# S7CAS-PLEIADES-CARTE-MERE_P06_ADC.net
KiCad netlist of a schematic drawn in Altium Designer
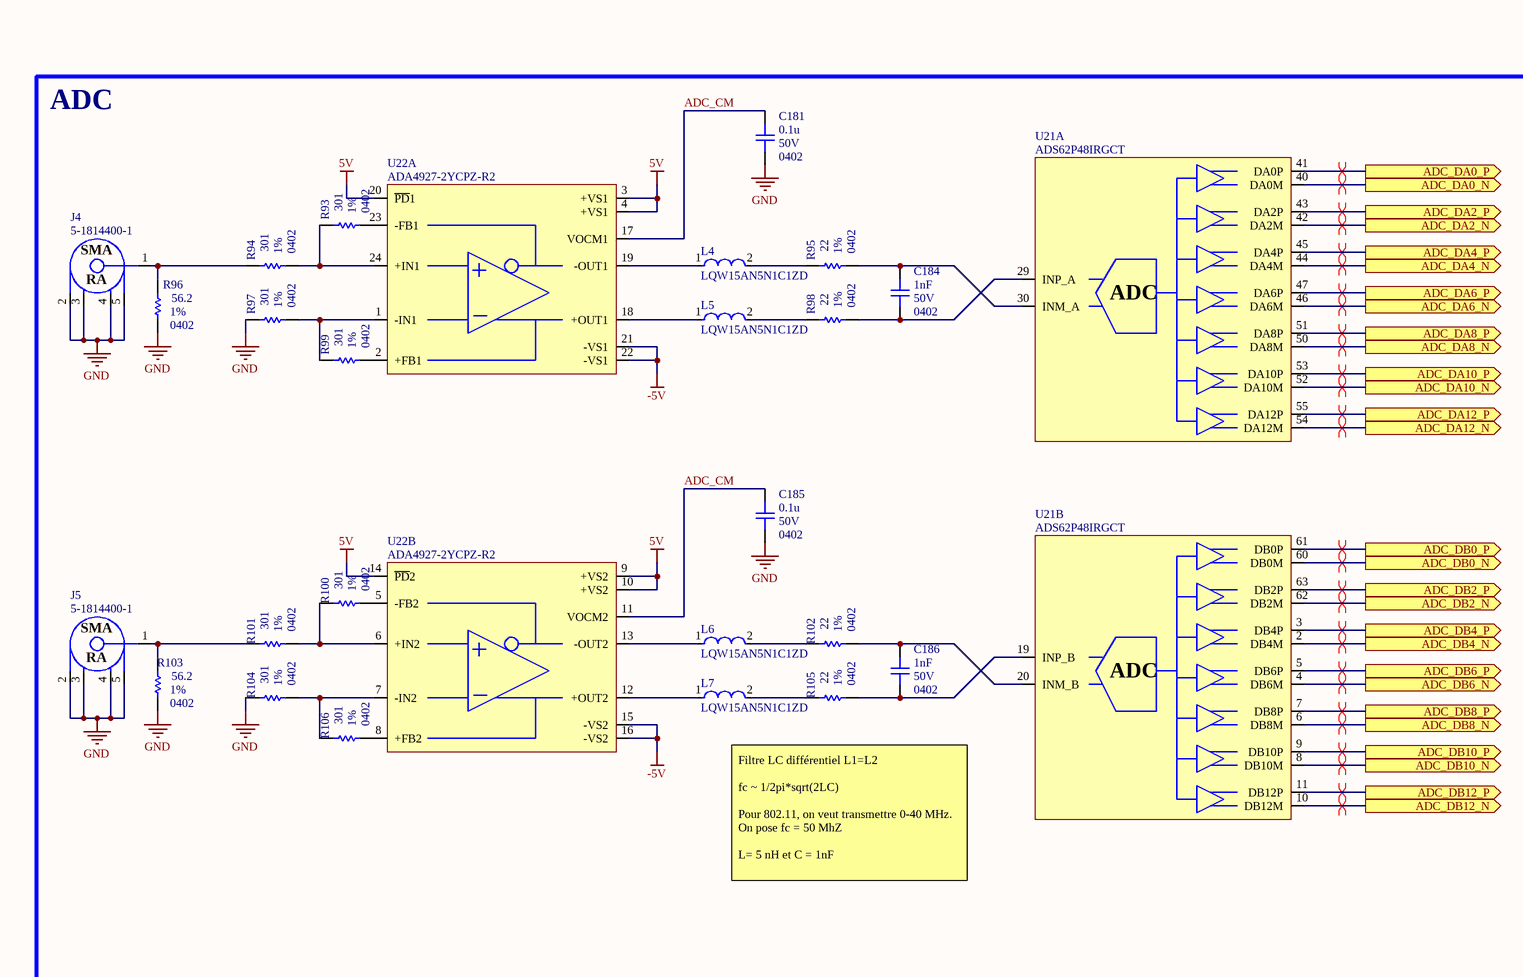
[diagram p0: S7CAS-PLEIADES-CARTE-MERE_P06_ADC.SchDoc, top left]
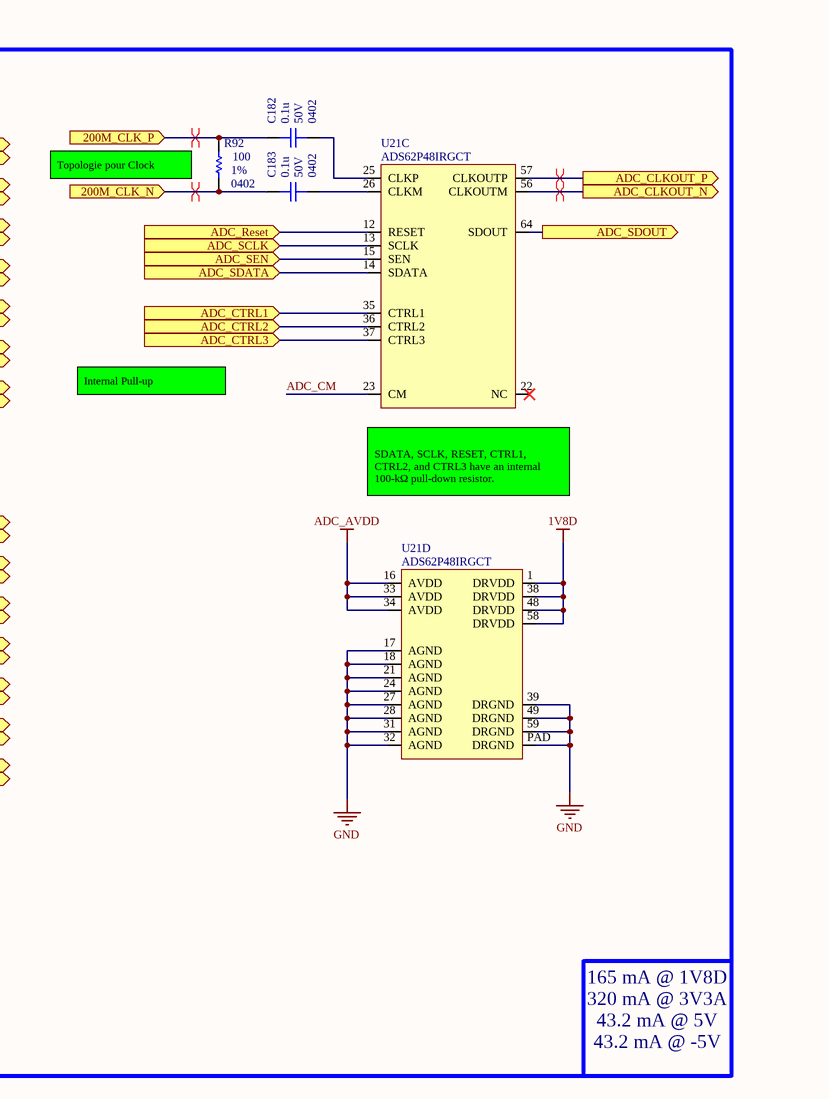
[diagram p1: S7CAS-PLEIADES-CARTE-MERE_P06_ADC.SchDoc, top middle]
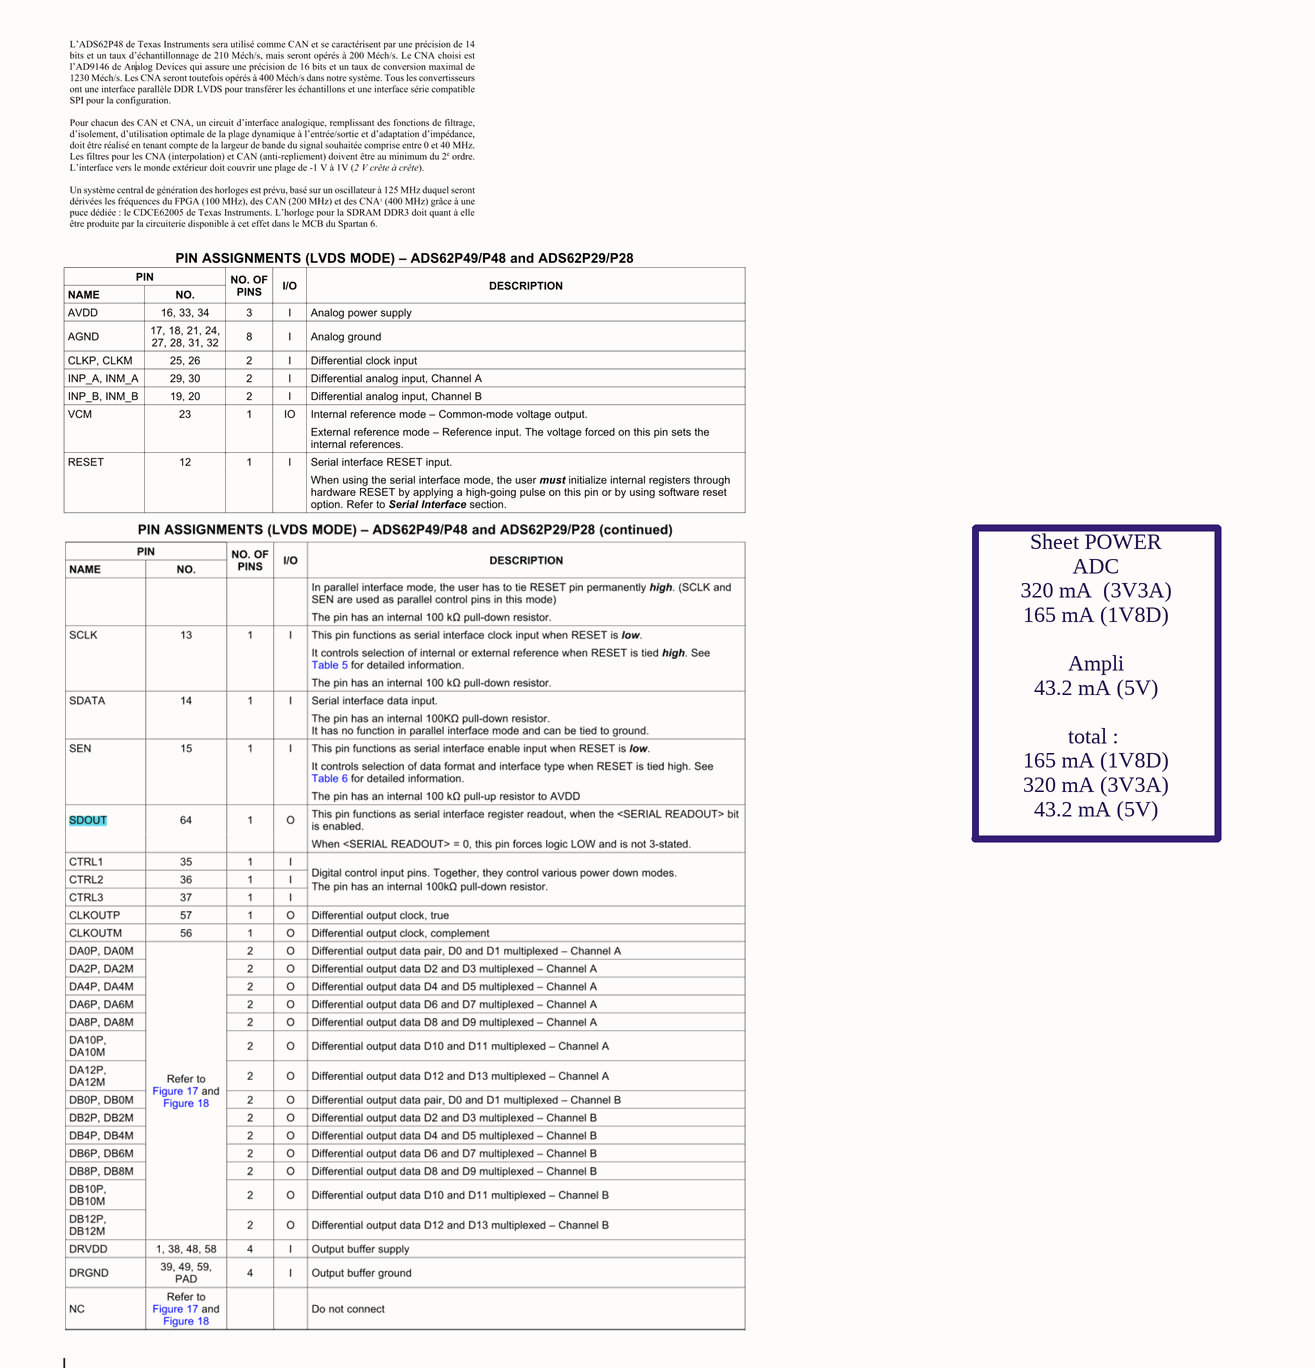
[diagram p2: S7CAS-PLEIADES-CARTE-MERE_P06_ADC.SchDoc, top right]
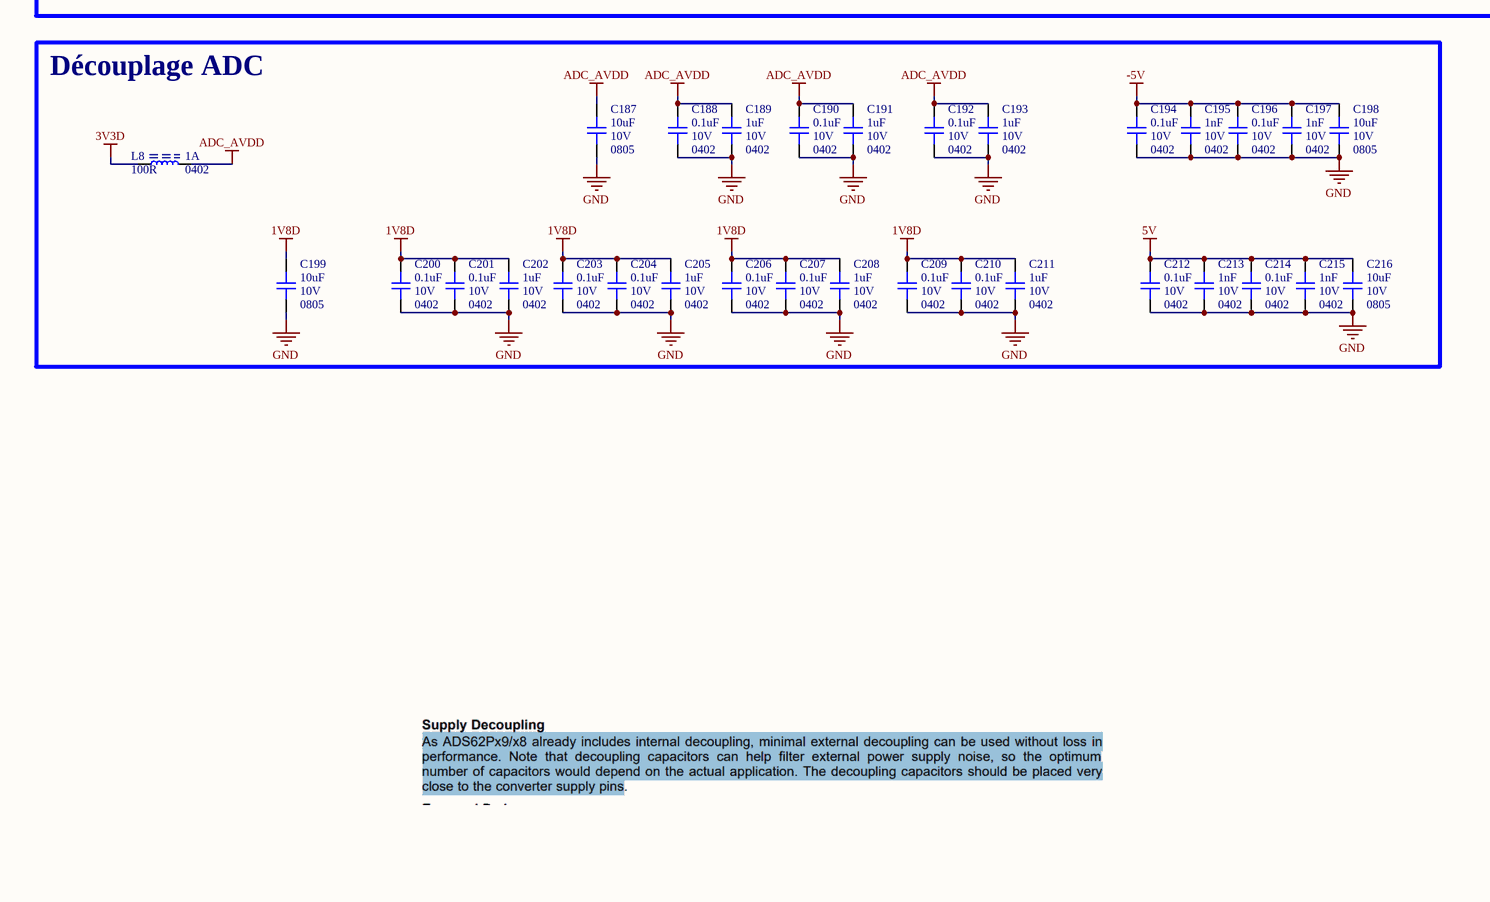
[diagram p3: S7CAS-PLEIADES-CARTE-MERE_P06_ADC.SchDoc, bottom left]
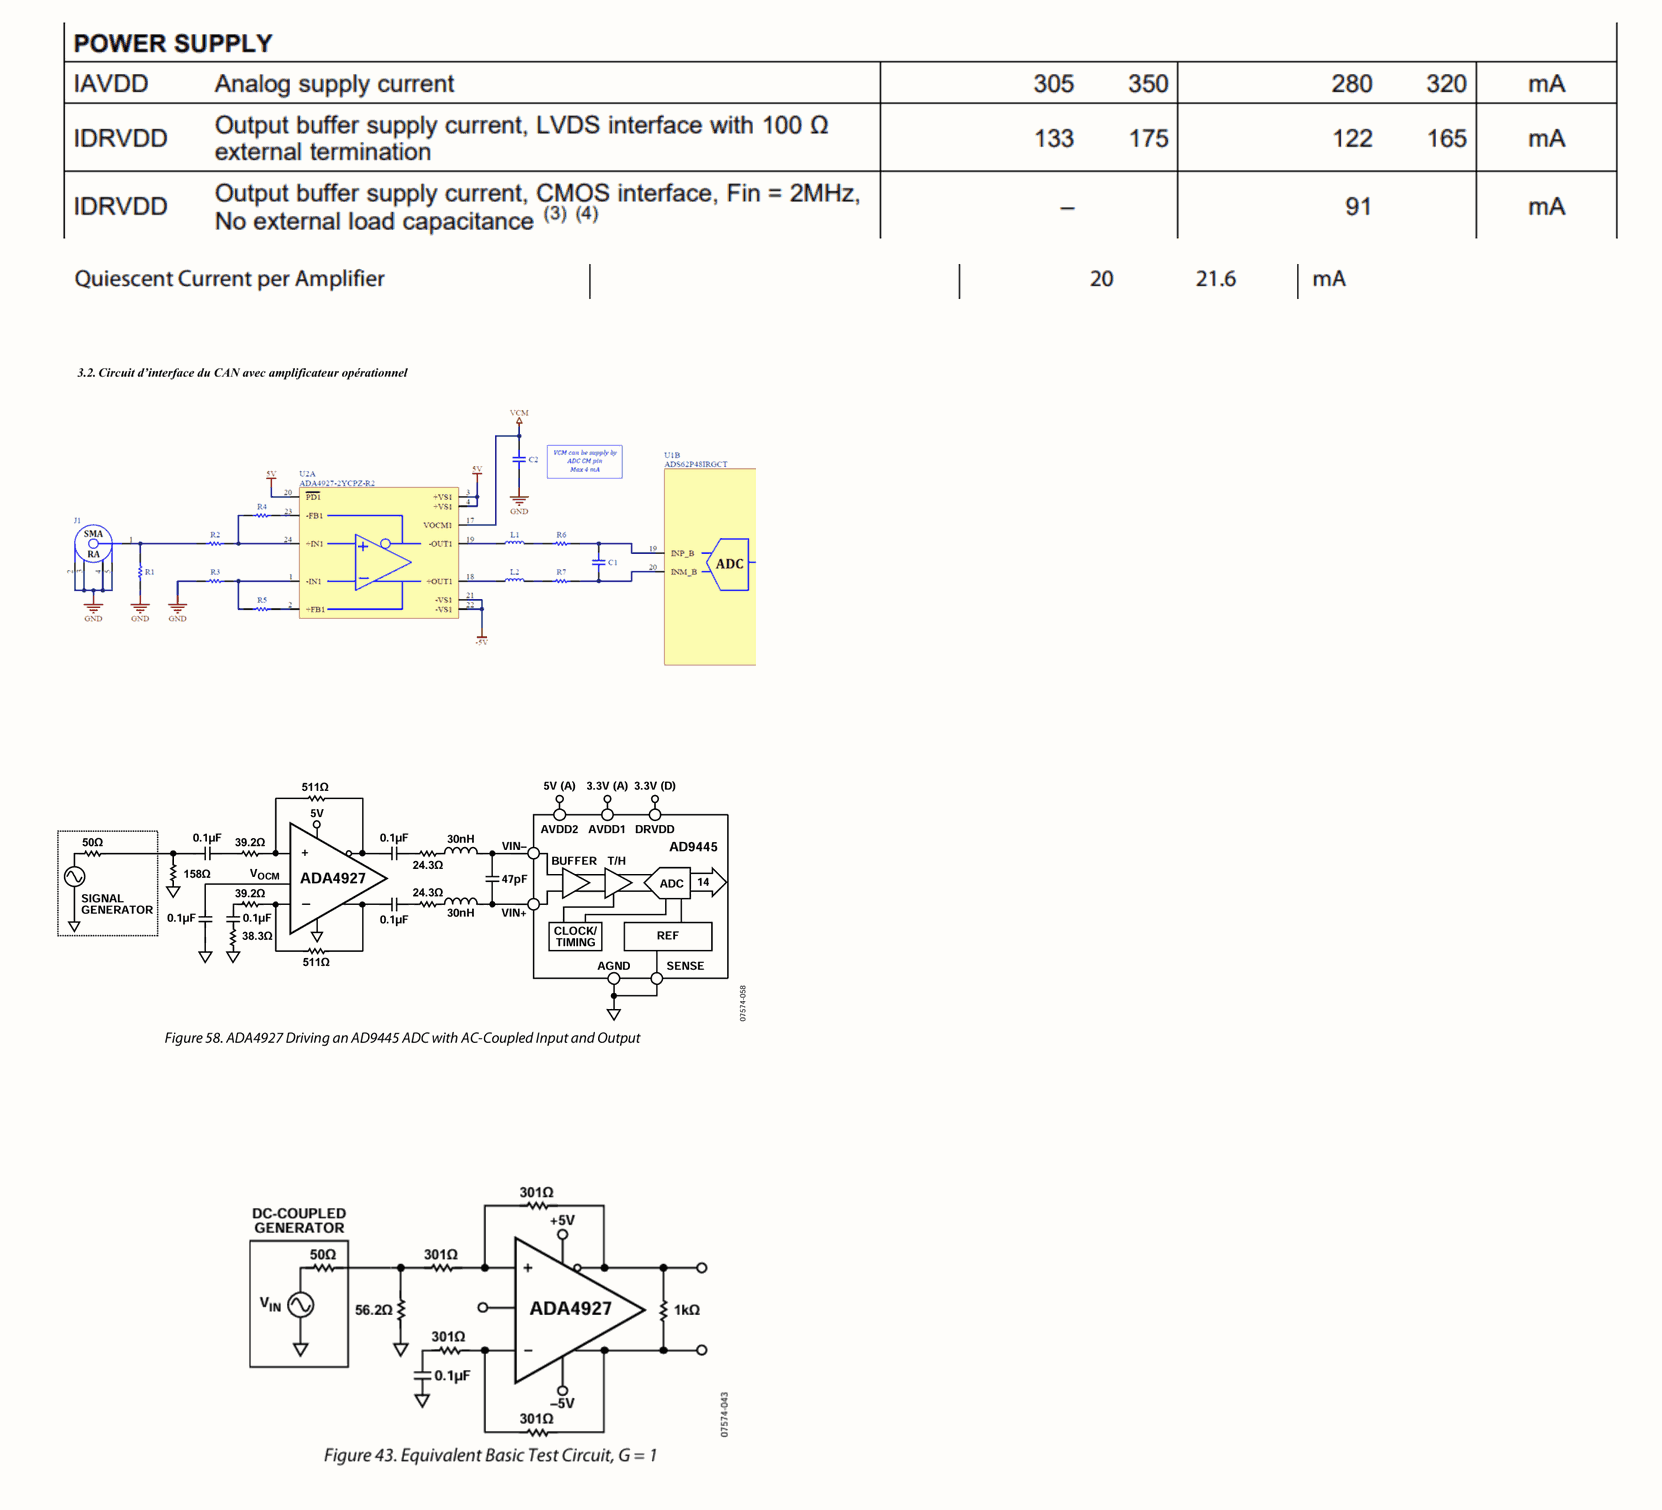
[diagram p4: S7CAS-PLEIADES-CARTE-MERE_P06_ADC.SchDoc, bottom right]

(export (version "E")
  (design (tool "Eeschema 10.0.6"))
  (components
    (comp (ref "C181")
      (value "0.1u")
      (footprint "CAP_0402")
      (description "CAP - 0402")
      (fields
        (field (name "VOLTAGE") "50V")
        (field (name "PACKAGE") "0402")
        (field (name "CREATEDBY") "Jonathan Bouchard")
      )
      (libsource (lib "s7cas_lib2023") (part "CAP - 0402"))
    )
    (comp (ref "C182")
      (value "0.1u")
      (footprint "CAP_0402")
      (description "CAP - 0402")
      (fields
        (field (name "VOLTAGE") "50V")
        (field (name "PACKAGE") "0402")
        (field (name "CREATEDBY") "Jonathan Bouchard")
      )
      (libsource (lib "s7cas_lib2023") (part "CAP - 0402"))
    )
    (comp (ref "C183")
      (value "0.1u")
      (footprint "CAP_0402")
      (description "CAP - 0402")
      (fields
        (field (name "VOLTAGE") "50V")
        (field (name "PACKAGE") "0402")
        (field (name "CREATEDBY") "Jonathan Bouchard")
      )
      (libsource (lib "s7cas_lib2023") (part "CAP - 0402"))
    )
    (comp (ref "C184")
      (value "1nF")
      (footprint "CAP_0402")
      (description "CAP - 0402")
      (fields
        (field (name "MFG PART NUMBER") "GCM1555C1H102FA16D")
        (field (name "VOLTAGE") "50V")
        (field (name "PACKAGE") "0402")
        (field (name "CREATEDBY") "Jonathan Bouchard")
      )
      (libsource (lib "s7cas_lib2023") (part "CAP - 0402"))
    )
    (comp (ref "C185")
      (value "0.1u")
      (footprint "CAP_0402")
      (description "CAP - 0402")
      (fields
        (field (name "VOLTAGE") "50V")
        (field (name "PACKAGE") "0402")
        (field (name "CREATEDBY") "Jonathan Bouchard")
      )
      (libsource (lib "s7cas_lib2023") (part "CAP - 0402"))
    )
    (comp (ref "C186")
      (value "1nF")
      (footprint "CAP_0402")
      (description "CAP - 0402")
      (fields
        (field (name "MFG PART NUMBER") "GCM1555C1H102FA16D")
        (field (name "VOLTAGE") "50V")
        (field (name "PACKAGE") "0402")
        (field (name "CREATEDBY") "Jonathan Bouchard")
      )
      (libsource (lib "s7cas_lib2023") (part "CAP - 0402"))
    )
    (comp (ref "C187")
      (value "10uF")
      (footprint "CAP_0805")
      (description "CAP - 0805")
      (fields
        (field (name "VOLTAGE") "10V")
        (field (name "PACKAGE") "0805")
        (field (name "CREATEDBY") "Jonathan Bouchard")
      )
      (libsource (lib "s7cas_lib2023") (part "CAP - 0805"))
    )
    (comp (ref "C188")
      (value "0.1uF")
      (footprint "CAP_0402")
      (description "CAP - 0402")
      (fields
        (field (name "VOLTAGE") "10V")
        (field (name "PACKAGE") "0402")
        (field (name "CREATEDBY") "Jonathan Bouchard")
      )
      (libsource (lib "s7cas_lib2023") (part "CAP - 0402"))
    )
    (comp (ref "C189")
      (value "1uF")
      (footprint "CAP_0402")
      (description "CAP - 0402")
      (fields
        (field (name "VOLTAGE") "10V")
        (field (name "PACKAGE") "0402")
        (field (name "CREATEDBY") "Jonathan Bouchard")
      )
      (libsource (lib "s7cas_lib2023") (part "CAP - 0402"))
    )
    (comp (ref "C190")
      (value "0.1uF")
      (footprint "CAP_0402")
      (description "CAP - 0402")
      (fields
        (field (name "VOLTAGE") "10V")
        (field (name "PACKAGE") "0402")
        (field (name "CREATEDBY") "Jonathan Bouchard")
      )
      (libsource (lib "s7cas_lib2023") (part "CAP - 0402"))
    )
    (comp (ref "C191")
      (value "1uF")
      (footprint "CAP_0402")
      (description "CAP - 0402")
      (fields
        (field (name "VOLTAGE") "10V")
        (field (name "PACKAGE") "0402")
        (field (name "CREATEDBY") "Jonathan Bouchard")
      )
      (libsource (lib "s7cas_lib2023") (part "CAP - 0402"))
    )
    (comp (ref "C192")
      (value "0.1uF")
      (footprint "CAP_0402")
      (description "CAP - 0402")
      (fields
        (field (name "VOLTAGE") "10V")
        (field (name "PACKAGE") "0402")
        (field (name "CREATEDBY") "Jonathan Bouchard")
      )
      (libsource (lib "s7cas_lib2023") (part "CAP - 0402"))
    )
    (comp (ref "C193")
      (value "1uF")
      (footprint "CAP_0402")
      (description "CAP - 0402")
      (fields
        (field (name "VOLTAGE") "10V")
        (field (name "PACKAGE") "0402")
        (field (name "CREATEDBY") "Jonathan Bouchard")
      )
      (libsource (lib "s7cas_lib2023") (part "CAP - 0402"))
    )
    (comp (ref "C194")
      (value "0.1uF")
      (footprint "CAP_0402")
      (description "CAP - 0402")
      (fields
        (field (name "VOLTAGE") "10V")
        (field (name "PACKAGE") "0402")
        (field (name "CREATEDBY") "Jonathan Bouchard")
      )
      (libsource (lib "s7cas_lib2023") (part "CAP - 0402"))
    )
    (comp (ref "C195")
      (value "1nF")
      (footprint "CAP_0402")
      (description "CAP - 0402")
      (fields
        (field (name "VOLTAGE") "10V")
        (field (name "PACKAGE") "0402")
        (field (name "CREATEDBY") "Jonathan Bouchard")
      )
      (libsource (lib "s7cas_lib2023") (part "CAP - 0402"))
    )
    (comp (ref "C196")
      (value "0.1uF")
      (footprint "CAP_0402")
      (description "CAP - 0402")
      (fields
        (field (name "VOLTAGE") "10V")
        (field (name "PACKAGE") "0402")
        (field (name "CREATEDBY") "Jonathan Bouchard")
      )
      (libsource (lib "s7cas_lib2023") (part "CAP - 0402"))
    )
    (comp (ref "C197")
      (value "1nF")
      (footprint "CAP_0402")
      (description "CAP - 0402")
      (fields
        (field (name "VOLTAGE") "10V")
        (field (name "PACKAGE") "0402")
        (field (name "CREATEDBY") "Jonathan Bouchard")
      )
      (libsource (lib "s7cas_lib2023") (part "CAP - 0402"))
    )
    (comp (ref "C198")
      (value "10uF")
      (footprint "CAP_0805")
      (description "CAP - 0805")
      (fields
        (field (name "VOLTAGE") "10V")
        (field (name "PACKAGE") "0805")
        (field (name "CREATEDBY") "Jonathan Bouchard")
      )
      (libsource (lib "s7cas_lib2023") (part "CAP - 0805"))
    )
    (comp (ref "C199")
      (value "10uF")
      (footprint "CAP_0805")
      (description "CAP - 0805")
      (fields
        (field (name "VOLTAGE") "10V")
        (field (name "PACKAGE") "0805")
        (field (name "CREATEDBY") "Jonathan Bouchard")
      )
      (libsource (lib "s7cas_lib2023") (part "CAP - 0805"))
    )
    (comp (ref "C200")
      (value "0.1uF")
      (footprint "CAP_0402")
      (description "CAP - 0402")
      (fields
        (field (name "VOLTAGE") "10V")
        (field (name "PACKAGE") "0402")
        (field (name "CREATEDBY") "Jonathan Bouchard")
      )
      (libsource (lib "s7cas_lib2023") (part "CAP - 0402"))
    )
    (comp (ref "C201")
      (value "0.1uF")
      (footprint "CAP_0402")
      (description "CAP - 0402")
      (fields
        (field (name "VOLTAGE") "10V")
        (field (name "PACKAGE") "0402")
        (field (name "CREATEDBY") "Jonathan Bouchard")
      )
      (libsource (lib "s7cas_lib2023") (part "CAP - 0402"))
    )
    (comp (ref "C202")
      (value "1uF")
      (footprint "CAP_0402")
      (description "CAP - 0402")
      (fields
        (field (name "VOLTAGE") "10V")
        (field (name "PACKAGE") "0402")
        (field (name "CREATEDBY") "Jonathan Bouchard")
      )
      (libsource (lib "s7cas_lib2023") (part "CAP - 0402"))
    )
    (comp (ref "C203")
      (value "0.1uF")
      (footprint "CAP_0402")
      (description "CAP - 0402")
      (fields
        (field (name "VOLTAGE") "10V")
        (field (name "PACKAGE") "0402")
        (field (name "CREATEDBY") "Jonathan Bouchard")
      )
      (libsource (lib "s7cas_lib2023") (part "CAP - 0402"))
    )
    (comp (ref "C204")
      (value "0.1uF")
      (footprint "CAP_0402")
      (description "CAP - 0402")
      (fields
        (field (name "VOLTAGE") "10V")
        (field (name "PACKAGE") "0402")
        (field (name "CREATEDBY") "Jonathan Bouchard")
      )
      (libsource (lib "s7cas_lib2023") (part "CAP - 0402"))
    )
    (comp (ref "C205")
      (value "1uF")
      (footprint "CAP_0402")
      (description "CAP - 0402")
      (fields
        (field (name "VOLTAGE") "10V")
        (field (name "PACKAGE") "0402")
        (field (name "CREATEDBY") "Jonathan Bouchard")
      )
      (libsource (lib "s7cas_lib2023") (part "CAP - 0402"))
    )
    (comp (ref "C206")
      (value "0.1uF")
      (footprint "CAP_0402")
      (description "CAP - 0402")
      (fields
        (field (name "VOLTAGE") "10V")
        (field (name "PACKAGE") "0402")
        (field (name "CREATEDBY") "Jonathan Bouchard")
      )
      (libsource (lib "s7cas_lib2023") (part "CAP - 0402"))
    )
    (comp (ref "C207")
      (value "0.1uF")
      (footprint "CAP_0402")
      (description "CAP - 0402")
      (fields
        (field (name "VOLTAGE") "10V")
        (field (name "PACKAGE") "0402")
        (field (name "CREATEDBY") "Jonathan Bouchard")
      )
      (libsource (lib "s7cas_lib2023") (part "CAP - 0402"))
    )
    (comp (ref "C208")
      (value "1uF")
      (footprint "CAP_0402")
      (description "CAP - 0402")
      (fields
        (field (name "VOLTAGE") "10V")
        (field (name "PACKAGE") "0402")
        (field (name "CREATEDBY") "Jonathan Bouchard")
      )
      (libsource (lib "s7cas_lib2023") (part "CAP - 0402"))
    )
    (comp (ref "C209")
      (value "0.1uF")
      (footprint "CAP_0402")
      (description "CAP - 0402")
      (fields
        (field (name "VOLTAGE") "10V")
        (field (name "PACKAGE") "0402")
        (field (name "CREATEDBY") "Jonathan Bouchard")
      )
      (libsource (lib "s7cas_lib2023") (part "CAP - 0402"))
    )
    (comp (ref "C210")
      (value "0.1uF")
      (footprint "CAP_0402")
      (description "CAP - 0402")
      (fields
        (field (name "VOLTAGE") "10V")
        (field (name "PACKAGE") "0402")
        (field (name "CREATEDBY") "Jonathan Bouchard")
      )
      (libsource (lib "s7cas_lib2023") (part "CAP - 0402"))
    )
    (comp (ref "C211")
      (value "1uF")
      (footprint "CAP_0402")
      (description "CAP - 0402")
      (fields
        (field (name "VOLTAGE") "10V")
        (field (name "PACKAGE") "0402")
        (field (name "CREATEDBY") "Jonathan Bouchard")
      )
      (libsource (lib "s7cas_lib2023") (part "CAP - 0402"))
    )
    (comp (ref "C212")
      (value "0.1uF")
      (footprint "CAP_0402")
      (description "CAP - 0402")
      (fields
        (field (name "VOLTAGE") "10V")
        (field (name "PACKAGE") "0402")
        (field (name "CREATEDBY") "Jonathan Bouchard")
      )
      (libsource (lib "s7cas_lib2023") (part "CAP - 0402"))
    )
    (comp (ref "C213")
      (value "1nF")
      (footprint "CAP_0402")
      (description "CAP - 0402")
      (fields
        (field (name "VOLTAGE") "10V")
        (field (name "PACKAGE") "0402")
        (field (name "CREATEDBY") "Jonathan Bouchard")
      )
      (libsource (lib "s7cas_lib2023") (part "CAP - 0402"))
    )
    (comp (ref "C214")
      (value "0.1uF")
      (footprint "CAP_0402")
      (description "CAP - 0402")
      (fields
        (field (name "VOLTAGE") "10V")
        (field (name "PACKAGE") "0402")
        (field (name "CREATEDBY") "Jonathan Bouchard")
      )
      (libsource (lib "s7cas_lib2023") (part "CAP - 0402"))
    )
    (comp (ref "C215")
      (value "1nF")
      (footprint "CAP_0402")
      (description "CAP - 0402")
      (fields
        (field (name "VOLTAGE") "10V")
        (field (name "PACKAGE") "0402")
        (field (name "CREATEDBY") "Jonathan Bouchard")
      )
      (libsource (lib "s7cas_lib2023") (part "CAP - 0402"))
    )
    (comp (ref "C216")
      (value "10uF")
      (footprint "CAP_0805")
      (description "CAP - 0805")
      (fields
        (field (name "VOLTAGE") "10V")
        (field (name "PACKAGE") "0805")
        (field (name "CREATEDBY") "Jonathan Bouchard")
      )
      (libsource (lib "s7cas_lib2023") (part "CAP - 0805"))
    )
    (comp (ref "J4")
      (value "5-1814400-1")
      (footprint "CONN_SMA_5-1814400-1")
      (description "CONN -  SMA JACK R/A 50 OHM - TH")
      (fields
        (field (name "MFG") "TE Connectivity AMP Connectors")
        (field (name "CREATEDBY") "Jonathan Bouchard")
      )
      (libsource (lib "s7cas_lib2023") (part "CONN_SMA_5-1814400-1"))
    )
    (comp (ref "J5")
      (value "5-1814400-1")
      (footprint "CONN_SMA_5-1814400-1")
      (description "CONN -  SMA JACK R/A 50 OHM - TH")
      (fields
        (field (name "MFG") "TE Connectivity AMP Connectors")
        (field (name "CREATEDBY") "Jonathan Bouchard")
      )
      (libsource (lib "s7cas_lib2023") (part "CONN_SMA_5-1814400-1"))
    )
    (comp (ref "L4")
      (value "LQW15AN5N1C1ZD")
      (footprint "FP-LQW15AN_00-W0_6-0_1-MFG")
      (description "Wire Wound RF Inductor for Automotive 5.1nH ±0.2nH 800mA 0.051Ω 0402 (1005)")
      (libsource (lib "Altium Content Vault") (part "725321dda6339637d4d059423bc1c3c"))
    )
    (comp (ref "L5")
      (value "LQW15AN5N1C1ZD")
      (footprint "FP-LQW15AN_00-W0_6-0_1-MFG")
      (description "Wire Wound RF Inductor for Automotive 5.1nH ±0.2nH 800mA 0.051Ω 0402 (1005)")
      (libsource (lib "Altium Content Vault") (part "725321dda6339637d4d059423bc1c3c"))
    )
    (comp (ref "L6")
      (value "LQW15AN5N1C1ZD")
      (footprint "FP-LQW15AN_00-W0_6-0_1-MFG")
      (description "Wire Wound RF Inductor for Automotive 5.1nH ±0.2nH 800mA 0.051Ω 0402 (1005)")
      (libsource (lib "Altium Content Vault") (part "725321dda6339637d4d059423bc1c3c"))
    )
    (comp (ref "L7")
      (value "LQW15AN5N1C1ZD")
      (footprint "FP-LQW15AN_00-W0_6-0_1-MFG")
      (description "Wire Wound RF Inductor for Automotive 5.1nH ±0.2nH 800mA 0.051Ω 0402 (1005)")
      (libsource (lib "Altium Content Vault") (part "725321dda6339637d4d059423bc1c3c"))
    )
    (comp (ref "L8")
      (value "100R")
      (footprint "FER_0402")
      (description "FER - 0402")
      (fields
        (field (name "CURRENT") "1A")
        (field (name "PACKAGE") "0402")
        (field (name "CREATEDBY") "Jonathan Bouchard")
      )
      (libsource (lib "s7cas_lib2023") (part "FER - 0402"))
    )
    (comp (ref "R92")
      (value "100")
      (footprint "RES_0402")
      (description "RES - 0402")
      (fields
        (field (name "VOLTAGE") "50V")
        (field (name "POWER") "1/16W")
        (field (name "PACKAGE") "0402")
        (field (name "PRECISION") "1%")
        (field (name "CREATEDBY") "Jonathan Bouchard")
      )
      (libsource (lib "s7cas_lib2023") (part "RES - 0402"))
    )
    (comp (ref "R93")
      (value "301")
      (footprint "RES_0402")
      (description "RES - 0402")
      (fields
        (field (name "VOLTAGE") "50V")
        (field (name "POWER") "1/16W")
        (field (name "PACKAGE") "0402")
        (field (name "PRECISION") "1%")
        (field (name "CREATEDBY") "Jonathan Bouchard")
      )
      (libsource (lib "s7cas_lib2023") (part "RES - 0402"))
    )
    (comp (ref "R94")
      (value "301")
      (footprint "RES_0402")
      (description "RES - 0402")
      (fields
        (field (name "VOLTAGE") "50V")
        (field (name "POWER") "1/16W")
        (field (name "PACKAGE") "0402")
        (field (name "PRECISION") "1%")
        (field (name "CREATEDBY") "Jonathan Bouchard")
      )
      (libsource (lib "s7cas_lib2023") (part "RES - 0402"))
    )
    (comp (ref "R95")
      (value "22")
      (footprint "RES_0402")
      (description "RES - 0402")
      (fields
        (field (name "VOLTAGE") "50V")
        (field (name "POWER") "1/16W")
        (field (name "PACKAGE") "0402")
        (field (name "PRECISION") "1%")
        (field (name "CREATEDBY") "Jonathan Bouchard")
      )
      (libsource (lib "s7cas_lib2023") (part "RES - 0402"))
    )
    (comp (ref "R96")
      (value "56.2")
      (footprint "RES_0402")
      (description "RES - 0402")
      (fields
        (field (name "VOLTAGE") "50V")
        (field (name "POWER") "1/16W")
        (field (name "PACKAGE") "0402")
        (field (name "PRECISION") "1%")
        (field (name "CREATEDBY") "Jonathan Bouchard")
      )
      (libsource (lib "s7cas_lib2023") (part "RES - 0402"))
    )
    (comp (ref "R97")
      (value "301")
      (footprint "RES_0402")
      (description "RES - 0402")
      (fields
        (field (name "VOLTAGE") "50V")
        (field (name "POWER") "1/16W")
        (field (name "PACKAGE") "0402")
        (field (name "PRECISION") "1%")
        (field (name "CREATEDBY") "Jonathan Bouchard")
      )
      (libsource (lib "s7cas_lib2023") (part "RES - 0402"))
    )
    (comp (ref "R98")
      (value "22")
      (footprint "RES_0402")
      (description "RES - 0402")
      (fields
        (field (name "VOLTAGE") "50V")
        (field (name "POWER") "1/16W")
        (field (name "PACKAGE") "0402")
        (field (name "PRECISION") "1%")
        (field (name "CREATEDBY") "Jonathan Bouchard")
      )
      (libsource (lib "s7cas_lib2023") (part "RES - 0402"))
    )
    (comp (ref "R99")
      (value "301")
      (footprint "RES_0402")
      (description "RES - 0402")
      (fields
        (field (name "VOLTAGE") "50V")
        (field (name "POWER") "1/16W")
        (field (name "PACKAGE") "0402")
        (field (name "PRECISION") "1%")
        (field (name "CREATEDBY") "Jonathan Bouchard")
      )
      (libsource (lib "s7cas_lib2023") (part "RES - 0402"))
    )
    (comp (ref "R100")
      (value "301")
      (footprint "RES_0402")
      (description "RES - 0402")
      (fields
        (field (name "VOLTAGE") "50V")
        (field (name "POWER") "1/16W")
        (field (name "PACKAGE") "0402")
        (field (name "PRECISION") "1%")
        (field (name "CREATEDBY") "Jonathan Bouchard")
      )
      (libsource (lib "s7cas_lib2023") (part "RES - 0402"))
    )
    (comp (ref "R101")
      (value "301")
      (footprint "RES_0402")
      (description "RES - 0402")
      (fields
        (field (name "VOLTAGE") "50V")
        (field (name "POWER") "1/16W")
        (field (name "PACKAGE") "0402")
        (field (name "PRECISION") "1%")
        (field (name "CREATEDBY") "Jonathan Bouchard")
      )
      (libsource (lib "s7cas_lib2023") (part "RES - 0402"))
    )
    (comp (ref "R102")
      (value "22")
      (footprint "RES_0402")
      (description "RES - 0402")
      (fields
        (field (name "VOLTAGE") "50V")
        (field (name "POWER") "1/16W")
        (field (name "PACKAGE") "0402")
        (field (name "PRECISION") "1%")
        (field (name "CREATEDBY") "Jonathan Bouchard")
      )
      (libsource (lib "s7cas_lib2023") (part "RES - 0402"))
    )
    (comp (ref "R103")
      (value "56.2")
      (footprint "RES_0402")
      (description "RES - 0402")
      (fields
        (field (name "VOLTAGE") "50V")
        (field (name "POWER") "1/16W")
        (field (name "PACKAGE") "0402")
        (field (name "PRECISION") "1%")
        (field (name "CREATEDBY") "Jonathan Bouchard")
      )
      (libsource (lib "s7cas_lib2023") (part "RES - 0402"))
    )
    (comp (ref "R104")
      (value "301")
      (footprint "RES_0402")
      (description "RES - 0402")
      (fields
        (field (name "VOLTAGE") "50V")
        (field (name "POWER") "1/16W")
        (field (name "PACKAGE") "0402")
        (field (name "PRECISION") "1%")
        (field (name "CREATEDBY") "Jonathan Bouchard")
      )
      (libsource (lib "s7cas_lib2023") (part "RES - 0402"))
    )
    (comp (ref "R105")
      (value "22")
      (footprint "RES_0402")
      (description "RES - 0402")
      (fields
        (field (name "VOLTAGE") "50V")
        (field (name "POWER") "1/16W")
        (field (name "PACKAGE") "0402")
        (field (name "PRECISION") "1%")
        (field (name "CREATEDBY") "Jonathan Bouchard")
      )
      (libsource (lib "s7cas_lib2023") (part "RES - 0402"))
    )
    (comp (ref "R106")
      (value "301")
      (footprint "RES_0402")
      (description "RES - 0402")
      (fields
        (field (name "VOLTAGE") "50V")
        (field (name "POWER") "1/16W")
        (field (name "PACKAGE") "0402")
        (field (name "PRECISION") "1%")
        (field (name "CREATEDBY") "Jonathan Bouchard")
      )
      (libsource (lib "s7cas_lib2023") (part "RES - 0402"))
    )
    (comp (ref "U21")
      (value "ADS62P48IRGCT")
      (footprint "ADC_ADS62P48IRGCT")
      (description "ADC - 14 BIT 210MSPS SUAL - VQFN-64")
      (fields
        (field (name "VOLTAGE") "3.15 V ~ 3.6 V / 1.7 V ~ 1.9 V")
        (field (name "MFG") "Texas Instruments")
        (field (name "CREATEDBY") "Jonathan Bouchard")
      )
      (libsource (lib "s7cas_lib2023") (part "ADC_ADS62P48IRGCT"))
    )
    (comp (ref "U22")
      (value "ADA4927-2YCPZ-R2")
      (footprint "OPAMP_ADA4927-2YCPZ-R2")
      (description "OPAMP - CFA 2.3GHZ - QFN-24")
      (fields
        (field (name "VOLTAGE") "4.5 V ~ 11 V, ±2.25 V ~ 5.5 V")
        (field (name "MFG") "Analog Devices")
        (field (name "CREATEDBY") "Jonathan Bouchard")
      )
      (libsource (lib "s7cas_lib2023") (part "OPAMP_ADA4927-2YCPZ-R2"))
    )
  )
  (nets
    (net (code "1") (name "-5V") (class "Default")
      (node (ref "C194") (pin "2") (pinfunction "2_2") (pintype "passive"))
      (node (ref "C195") (pin "2") (pinfunction "2_2") (pintype "passive"))
      (node (ref "C196") (pin "2") (pinfunction "2_2") (pintype "passive"))
      (node (ref "C197") (pin "2") (pinfunction "2_2") (pintype "passive"))
      (node (ref "C198") (pin "2") (pinfunction "2_2") (pintype "passive"))
      (node (ref "U22") (pin "15") (pinfunction "-VS2_15") (pintype "passive"))
      (node (ref "U22") (pin "16") (pinfunction "-VS2_16") (pintype "passive"))
      (node (ref "U22") (pin "21") (pinfunction "-VS1_21") (pintype "passive"))
      (node (ref "U22") (pin "22") (pinfunction "-VS1_22") (pintype "passive"))
    )
    (net (code "2") (name "/200M_CLK_N") (class "Default")
      (node (ref "C183") (pin "2") (pinfunction "2_2") (pintype "passive"))
      (node (ref "R92") (pin "1") (pinfunction "1_1") (pintype "passive"))
    )
    (net (code "3") (name "/200M_CLK_P") (class "Default")
      (node (ref "C182") (pin "2") (pinfunction "2_2") (pintype "passive"))
      (node (ref "R92") (pin "2") (pinfunction "2_2") (pintype "passive"))
    )
    (net (code "4") (name "/ADC_CLKOUT_N") (class "Default")
      (node (ref "U21") (pin "56") (pinfunction "CLKOUTM_56") (pintype "passive"))
    )
    (net (code "5") (name "/ADC_CLKOUT_P") (class "Default")
      (node (ref "U21") (pin "57") (pinfunction "CLKOUTP_57") (pintype "passive"))
    )
    (net (code "6") (name "/ADC_CM") (class "Default")
      (node (ref "C181") (pin "2") (pinfunction "2_2") (pintype "passive"))
      (node (ref "C185") (pin "2") (pinfunction "2_2") (pintype "passive"))
      (node (ref "U21") (pin "23") (pinfunction "CM_23") (pintype "passive"))
      (node (ref "U22") (pin "11") (pinfunction "VOCM2_11") (pintype "passive"))
      (node (ref "U22") (pin "17") (pinfunction "VOCM1_17") (pintype "passive"))
    )
    (net (code "7") (name "/ADC_CTRL1") (class "Default")
      (node (ref "U21") (pin "35") (pinfunction "CTRL1_35") (pintype "passive"))
    )
    (net (code "8") (name "/ADC_CTRL2") (class "Default")
      (node (ref "U21") (pin "36") (pinfunction "CTRL2_36") (pintype "passive"))
    )
    (net (code "9") (name "/ADC_CTRL3") (class "Default")
      (node (ref "U21") (pin "37") (pinfunction "CTRL3_37") (pintype "passive"))
    )
    (net (code "10") (name "/ADC_DA0_N") (class "Default")
      (node (ref "U21") (pin "40") (pinfunction "DA0M_40") (pintype "passive"))
    )
    (net (code "11") (name "/ADC_DA0_P") (class "Default")
      (node (ref "U21") (pin "41") (pinfunction "DA0P_41") (pintype "passive"))
    )
    (net (code "12") (name "/ADC_DA2_N") (class "Default")
      (node (ref "U21") (pin "42") (pinfunction "DA2M_42") (pintype "passive"))
    )
    (net (code "13") (name "/ADC_DA2_P") (class "Default")
      (node (ref "U21") (pin "43") (pinfunction "DA2P_43") (pintype "passive"))
    )
    (net (code "14") (name "/ADC_DA4_N") (class "Default")
      (node (ref "U21") (pin "44") (pinfunction "DA4M_44") (pintype "passive"))
    )
    (net (code "15") (name "/ADC_DA4_P") (class "Default")
      (node (ref "U21") (pin "45") (pinfunction "DA4P_45") (pintype "passive"))
    )
    (net (code "16") (name "/ADC_DA6_N") (class "Default")
      (node (ref "U21") (pin "46") (pinfunction "DA6M_46") (pintype "passive"))
    )
    (net (code "17") (name "/ADC_DA6_P") (class "Default")
      (node (ref "U21") (pin "47") (pinfunction "DA6P_47") (pintype "passive"))
    )
    (net (code "18") (name "/ADC_DA8_N") (class "Default")
      (node (ref "U21") (pin "50") (pinfunction "DA8M_50") (pintype "passive"))
    )
    (net (code "19") (name "/ADC_DA8_P") (class "Default")
      (node (ref "U21") (pin "51") (pinfunction "DA8P_51") (pintype "passive"))
    )
    (net (code "20") (name "/ADC_DA10_N") (class "Default")
      (node (ref "U21") (pin "52") (pinfunction "DA10M_52") (pintype "passive"))
    )
    (net (code "21") (name "/ADC_DA10_P") (class "Default")
      (node (ref "U21") (pin "53") (pinfunction "DA10P_53") (pintype "passive"))
    )
    (net (code "22") (name "/ADC_DA12_N") (class "Default")
      (node (ref "U21") (pin "54") (pinfunction "DA12M_54") (pintype "passive"))
    )
    (net (code "23") (name "/ADC_DA12_P") (class "Default")
      (node (ref "U21") (pin "55") (pinfunction "DA12P_55") (pintype "passive"))
    )
    (net (code "24") (name "/ADC_DB0_N") (class "Default")
      (node (ref "U21") (pin "60") (pinfunction "DB0M_60") (pintype "passive"))
    )
    (net (code "25") (name "/ADC_DB0_P") (class "Default")
      (node (ref "U21") (pin "61") (pinfunction "DB0P_61") (pintype "passive"))
    )
    (net (code "26") (name "/ADC_DB2_N") (class "Default")
      (node (ref "U21") (pin "62") (pinfunction "DB2M_62") (pintype "passive"))
    )
    (net (code "27") (name "/ADC_DB2_P") (class "Default")
      (node (ref "U21") (pin "63") (pinfunction "DB2P_63") (pintype "passive"))
    )
    (net (code "28") (name "/ADC_DB4_N") (class "Default")
      (node (ref "U21") (pin "2") (pinfunction "DB4M_2") (pintype "passive"))
    )
    (net (code "29") (name "/ADC_DB4_P") (class "Default")
      (node (ref "U21") (pin "3") (pinfunction "DB4P_3") (pintype "passive"))
    )
    (net (code "30") (name "/ADC_DB6_N") (class "Default")
      (node (ref "U21") (pin "4") (pinfunction "DB6M_4") (pintype "passive"))
    )
    (net (code "31") (name "/ADC_DB6_P") (class "Default")
      (node (ref "U21") (pin "5") (pinfunction "DB6P_5") (pintype "passive"))
    )
    (net (code "32") (name "/ADC_DB8_N") (class "Default")
      (node (ref "U21") (pin "6") (pinfunction "DB8M_6") (pintype "passive"))
    )
    (net (code "33") (name "/ADC_DB8_P") (class "Default")
      (node (ref "U21") (pin "7") (pinfunction "DB8P_7") (pintype "passive"))
    )
    (net (code "34") (name "/ADC_DB10_N") (class "Default")
      (node (ref "U21") (pin "8") (pinfunction "DB10M_8") (pintype "passive"))
    )
    (net (code "35") (name "/ADC_DB10_P") (class "Default")
      (node (ref "U21") (pin "9") (pinfunction "DB10P_9") (pintype "passive"))
    )
    (net (code "36") (name "/ADC_DB12_N") (class "Default")
      (node (ref "U21") (pin "10") (pinfunction "DB12M_10") (pintype "passive"))
    )
    (net (code "37") (name "/ADC_DB12_P") (class "Default")
      (node (ref "U21") (pin "11") (pinfunction "DB12P_11") (pintype "passive"))
    )
    (net (code "38") (name "/ADC_Reset") (class "Default")
      (node (ref "U21") (pin "12") (pinfunction "RESET_12") (pintype "passive"))
    )
    (net (code "39") (name "/ADC_SCLK") (class "Default")
      (node (ref "U21") (pin "13") (pinfunction "SCLK_13") (pintype "passive"))
    )
    (net (code "40") (name "/ADC_SDATA") (class "Default")
      (node (ref "U21") (pin "14") (pinfunction "SDATA_14") (pintype "passive"))
    )
    (net (code "41") (name "/ADC_SDOUT") (class "Default")
      (node (ref "U21") (pin "64") (pinfunction "SDOUT_64") (pintype "passive"))
    )
    (net (code "42") (name "/ADC_SEN") (class "Default")
      (node (ref "U21") (pin "15") (pinfunction "SEN_15") (pintype "passive"))
    )
    (net (code "43") (name "1V8D") (class "Default")
      (node (ref "C199") (pin "2") (pinfunction "2_2") (pintype "passive"))
      (node (ref "C200") (pin "2") (pinfunction "2_2") (pintype "passive"))
      (node (ref "C201") (pin "2") (pinfunction "2_2") (pintype "passive"))
      (node (ref "C202") (pin "2") (pinfunction "2_2") (pintype "passive"))
      (node (ref "C203") (pin "2") (pinfunction "2_2") (pintype "passive"))
      (node (ref "C204") (pin "2") (pinfunction "2_2") (pintype "passive"))
      (node (ref "C205") (pin "2") (pinfunction "2_2") (pintype "passive"))
      (node (ref "C206") (pin "2") (pinfunction "2_2") (pintype "passive"))
      (node (ref "C207") (pin "2") (pinfunction "2_2") (pintype "passive"))
      (node (ref "C208") (pin "2") (pinfunction "2_2") (pintype "passive"))
      (node (ref "C209") (pin "2") (pinfunction "2_2") (pintype "passive"))
      (node (ref "C210") (pin "2") (pinfunction "2_2") (pintype "passive"))
      (node (ref "C211") (pin "2") (pinfunction "2_2") (pintype "passive"))
      (node (ref "U21") (pin "1") (pinfunction "DRVDD_1") (pintype "passive"))
      (node (ref "U21") (pin "38") (pinfunction "DRVDD_38") (pintype "passive"))
      (node (ref "U21") (pin "48") (pinfunction "DRVDD_48") (pintype "passive"))
      (node (ref "U21") (pin "58") (pinfunction "DRVDD_58") (pintype "passive"))
    )
    (net (code "44") (name "3V3D") (class "Default")
      (node (ref "L8") (pin "2") (pinfunction "2_2") (pintype "passive"))
    )
    (net (code "45") (name "5V") (class "Default")
      (node (ref "C212") (pin "2") (pinfunction "2_2") (pintype "passive"))
      (node (ref "C213") (pin "2") (pinfunction "2_2") (pintype "passive"))
      (node (ref "C214") (pin "2") (pinfunction "2_2") (pintype "passive"))
      (node (ref "C215") (pin "2") (pinfunction "2_2") (pintype "passive"))
      (node (ref "C216") (pin "2") (pinfunction "2_2") (pintype "passive"))
      (node (ref "U22") (pin "10") (pinfunction "+VS2_10") (pintype "passive"))
      (node (ref "U22") (pin "14") (pinfunction "~{PD}2_14") (pintype "passive"))
      (node (ref "U22") (pin "20") (pinfunction "~{PD}1_20") (pintype "passive"))
      (node (ref "U22") (pin "3") (pinfunction "+VS1_3") (pintype "passive"))
      (node (ref "U22") (pin "4") (pinfunction "+VS1_4") (pintype "passive"))
      (node (ref "U22") (pin "9") (pinfunction "+VS2_9") (pintype "passive"))
    )
    (net (code "46") (name "ADC_AVDD") (class "Default")
      (node (ref "C187") (pin "2") (pinfunction "2_2") (pintype "passive"))
      (node (ref "C188") (pin "2") (pinfunction "2_2") (pintype "passive"))
      (node (ref "C189") (pin "2") (pinfunction "2_2") (pintype "passive"))
      (node (ref "C190") (pin "2") (pinfunction "2_2") (pintype "passive"))
      (node (ref "C191") (pin "2") (pinfunction "2_2") (pintype "passive"))
      (node (ref "C192") (pin "2") (pinfunction "2_2") (pintype "passive"))
      (node (ref "C193") (pin "2") (pinfunction "2_2") (pintype "passive"))
      (node (ref "L8") (pin "1") (pinfunction "1_1") (pintype "passive"))
      (node (ref "U21") (pin "16") (pinfunction "AVDD_16") (pintype "passive"))
      (node (ref "U21") (pin "33") (pinfunction "AVDD_33") (pintype "passive"))
      (node (ref "U21") (pin "34") (pinfunction "AVDD_34") (pintype "passive"))
    )
    (net (code "47") (name "GND") (class "Default")
      (node (ref "C181") (pin "1") (pinfunction "1_1") (pintype "passive"))
      (node (ref "C185") (pin "1") (pinfunction "1_1") (pintype "passive"))
      (node (ref "C187") (pin "1") (pinfunction "1_1") (pintype "passive"))
      (node (ref "C188") (pin "1") (pinfunction "1_1") (pintype "passive"))
      (node (ref "C189") (pin "1") (pinfunction "1_1") (pintype "passive"))
      (node (ref "C190") (pin "1") (pinfunction "1_1") (pintype "passive"))
      (node (ref "C191") (pin "1") (pinfunction "1_1") (pintype "passive"))
      (node (ref "C192") (pin "1") (pinfunction "1_1") (pintype "passive"))
      (node (ref "C193") (pin "1") (pinfunction "1_1") (pintype "passive"))
      (node (ref "C194") (pin "1") (pinfunction "1_1") (pintype "passive"))
      (node (ref "C195") (pin "1") (pinfunction "1_1") (pintype "passive"))
      (node (ref "C196") (pin "1") (pinfunction "1_1") (pintype "passive"))
      (node (ref "C197") (pin "1") (pinfunction "1_1") (pintype "passive"))
      (node (ref "C198") (pin "1") (pinfunction "1_1") (pintype "passive"))
      (node (ref "C199") (pin "1") (pinfunction "1_1") (pintype "passive"))
      (node (ref "C200") (pin "1") (pinfunction "1_1") (pintype "passive"))
      (node (ref "C201") (pin "1") (pinfunction "1_1") (pintype "passive"))
      (node (ref "C202") (pin "1") (pinfunction "1_1") (pintype "passive"))
      (node (ref "C203") (pin "1") (pinfunction "1_1") (pintype "passive"))
      (node (ref "C204") (pin "1") (pinfunction "1_1") (pintype "passive"))
      (node (ref "C205") (pin "1") (pinfunction "1_1") (pintype "passive"))
      (node (ref "C206") (pin "1") (pinfunction "1_1") (pintype "passive"))
      (node (ref "C207") (pin "1") (pinfunction "1_1") (pintype "passive"))
      (node (ref "C208") (pin "1") (pinfunction "1_1") (pintype "passive"))
      (node (ref "C209") (pin "1") (pinfunction "1_1") (pintype "passive"))
      (node (ref "C210") (pin "1") (pinfunction "1_1") (pintype "passive"))
      (node (ref "C211") (pin "1") (pinfunction "1_1") (pintype "passive"))
      (node (ref "C212") (pin "1") (pinfunction "1_1") (pintype "passive"))
      (node (ref "C213") (pin "1") (pinfunction "1_1") (pintype "passive"))
      (node (ref "C214") (pin "1") (pinfunction "1_1") (pintype "passive"))
      (node (ref "C215") (pin "1") (pinfunction "1_1") (pintype "passive"))
      (node (ref "C216") (pin "1") (pinfunction "1_1") (pintype "passive"))
      (node (ref "J4") (pin "2") (pinfunction "2_2") (pintype "passive"))
      (node (ref "J4") (pin "3") (pinfunction "3_3") (pintype "passive"))
      (node (ref "J4") (pin "4") (pinfunction "4_4") (pintype "passive"))
      (node (ref "J4") (pin "5") (pinfunction "5_5") (pintype "passive"))
      (node (ref "J5") (pin "2") (pinfunction "2_2") (pintype "passive"))
      (node (ref "J5") (pin "3") (pinfunction "3_3") (pintype "passive"))
      (node (ref "J5") (pin "4") (pinfunction "4_4") (pintype "passive"))
      (node (ref "J5") (pin "5") (pinfunction "5_5") (pintype "passive"))
      (node (ref "R103") (pin "1") (pinfunction "1_1") (pintype "passive"))
      (node (ref "R104") (pin "2") (pinfunction "2_2") (pintype "passive"))
      (node (ref "R96") (pin "1") (pinfunction "1_1") (pintype "passive"))
      (node (ref "R97") (pin "2") (pinfunction "2_2") (pintype "passive"))
      (node (ref "U21") (pin "17") (pinfunction "AGND_17") (pintype "passive"))
      (node (ref "U21") (pin "18") (pinfunction "AGND_18") (pintype "passive"))
      (node (ref "U21") (pin "21") (pinfunction "AGND_21") (pintype "passive"))
      (node (ref "U21") (pin "24") (pinfunction "AGND_24") (pintype "passive"))
      (node (ref "U21") (pin "27") (pinfunction "AGND_27") (pintype "passive"))
      (node (ref "U21") (pin "28") (pinfunction "AGND_28") (pintype "passive"))
      (node (ref "U21") (pin "31") (pinfunction "AGND_31") (pintype "passive"))
      (node (ref "U21") (pin "32") (pinfunction "AGND_32") (pintype "passive"))
      (node (ref "U21") (pin "39") (pinfunction "DRGND_39") (pintype "passive"))
      (node (ref "U21") (pin "49") (pinfunction "DRGND_49") (pintype "passive"))
      (node (ref "U21") (pin "59") (pinfunction "DRGND_59") (pintype "passive"))
      (node (ref "U21") (pin "PAD") (pinfunction "DRGND_PAD") (pintype "passive"))
    )
    (net (code "48") (name "Net-(J4-Pad1)") (class "Default")
      (node (ref "J4") (pin "1") (pinfunction "1_1") (pintype "passive"))
      (node (ref "R94") (pin "2") (pinfunction "2_2") (pintype "passive"))
      (node (ref "R96") (pin "2") (pinfunction "2_2") (pintype "passive"))
    )
    (net (code "49") (name "Net-(J5-Pad1)") (class "Default")
      (node (ref "J5") (pin "1") (pinfunction "1_1") (pintype "passive"))
      (node (ref "R101") (pin "2") (pinfunction "2_2") (pintype "passive"))
      (node (ref "R103") (pin "2") (pinfunction "2_2") (pintype "passive"))
    )
    (net (code "50") (name "Net-(L4-Pad2)") (class "Default")
      (node (ref "L4") (pin "2") (pinfunction "2_2") (pintype "passive"))
      (node (ref "R95") (pin "2") (pinfunction "2_2") (pintype "passive"))
    )
    (net (code "51") (name "Net-(L5-Pad2)") (class "Default")
      (node (ref "L5") (pin "2") (pinfunction "2_2") (pintype "passive"))
      (node (ref "R98") (pin "2") (pinfunction "2_2") (pintype "passive"))
    )
    (net (code "52") (name "Net-(L6-Pad2)") (class "Default")
      (node (ref "L6") (pin "2") (pinfunction "2_2") (pintype "passive"))
      (node (ref "R102") (pin "2") (pinfunction "2_2") (pintype "passive"))
    )
    (net (code "53") (name "Net-(L7-Pad2)") (class "Default")
      (node (ref "L7") (pin "2") (pinfunction "2_2") (pintype "passive"))
      (node (ref "R105") (pin "2") (pinfunction "2_2") (pintype "passive"))
    )
    (net (code "54") (name "Net-(U21A-INM_A)") (class "Default")
      (node (ref "C184") (pin "2") (pinfunction "2_2") (pintype "passive"))
      (node (ref "R95") (pin "1") (pinfunction "1_1") (pintype "passive"))
      (node (ref "U21") (pin "30") (pinfunction "INM_A_30") (pintype "passive"))
    )
    (net (code "55") (name "Net-(U21A-INP_A)") (class "Default")
      (node (ref "C184") (pin "1") (pinfunction "1_1") (pintype "passive"))
      (node (ref "R98") (pin "1") (pinfunction "1_1") (pintype "passive"))
      (node (ref "U21") (pin "29") (pinfunction "INP_A_29") (pintype "passive"))
    )
    (net (code "56") (name "Net-(U21B-INM_B)") (class "Default")
      (node (ref "C186") (pin "2") (pinfunction "2_2") (pintype "passive"))
      (node (ref "R102") (pin "1") (pinfunction "1_1") (pintype "passive"))
      (node (ref "U21") (pin "20") (pinfunction "INM_B_20") (pintype "passive"))
    )
    (net (code "57") (name "Net-(U21B-INP_B)") (class "Default")
      (node (ref "C186") (pin "1") (pinfunction "1_1") (pintype "passive"))
      (node (ref "R105") (pin "1") (pinfunction "1_1") (pintype "passive"))
      (node (ref "U21") (pin "19") (pinfunction "INP_B_19") (pintype "passive"))
    )
    (net (code "58") (name "Net-(U21C-CLKM)") (class "Default")
      (node (ref "C183") (pin "1") (pinfunction "1_1") (pintype "passive"))
      (node (ref "U21") (pin "26") (pinfunction "CLKM_26") (pintype "passive"))
    )
    (net (code "59") (name "Net-(U21C-CLKP)") (class "Default")
      (node (ref "C182") (pin "1") (pinfunction "1_1") (pintype "passive"))
      (node (ref "U21") (pin "25") (pinfunction "CLKP_25") (pintype "passive"))
    )
    (net (code "60") (name "Net-(U22A-+FB1)") (class "Default")
      (node (ref "R99") (pin "1") (pinfunction "1_1") (pintype "passive"))
      (node (ref "U22") (pin "2") (pinfunction "+FB1_2") (pintype "passive"))
    )
    (net (code "61") (name "Net-(U22A-+IN1)") (class "Default")
      (node (ref "R93") (pin "2") (pinfunction "2_2") (pintype "passive"))
      (node (ref "R94") (pin "1") (pinfunction "1_1") (pintype "passive"))
      (node (ref "U22") (pin "24") (pinfunction "+IN1_24") (pintype "passive"))
    )
    (net (code "62") (name "Net-(U22A-+OUT1)") (class "Default")
      (node (ref "L5") (pin "1") (pinfunction "1_1") (pintype "passive"))
      (node (ref "U22") (pin "18") (pinfunction "+OUT1_18") (pintype "passive"))
    )
    (net (code "63") (name "Net-(U22A--FB1)") (class "Default")
      (node (ref "R93") (pin "1") (pinfunction "1_1") (pintype "passive"))
      (node (ref "U22") (pin "23") (pinfunction "-FB1_23") (pintype "passive"))
    )
    (net (code "64") (name "Net-(U22A--IN1)") (class "Default")
      (node (ref "R97") (pin "1") (pinfunction "1_1") (pintype "passive"))
      (node (ref "R99") (pin "2") (pinfunction "2_2") (pintype "passive"))
      (node (ref "U22") (pin "1") (pinfunction "-IN1_1") (pintype "passive"))
    )
    (net (code "65") (name "Net-(U22A--OUT1)") (class "Default")
      (node (ref "L4") (pin "1") (pinfunction "1_1") (pintype "passive"))
      (node (ref "U22") (pin "19") (pinfunction "-OUT1_19") (pintype "passive"))
    )
    (net (code "66") (name "Net-(U22B-+FB2)") (class "Default")
      (node (ref "R106") (pin "1") (pinfunction "1_1") (pintype "passive"))
      (node (ref "U22") (pin "8") (pinfunction "+FB2_8") (pintype "passive"))
    )
    (net (code "67") (name "Net-(U22B-+IN2)") (class "Default")
      (node (ref "R100") (pin "2") (pinfunction "2_2") (pintype "passive"))
      (node (ref "R101") (pin "1") (pinfunction "1_1") (pintype "passive"))
      (node (ref "U22") (pin "6") (pinfunction "+IN2_6") (pintype "passive"))
    )
    (net (code "68") (name "Net-(U22B-+OUT2)") (class "Default")
      (node (ref "L7") (pin "1") (pinfunction "1_1") (pintype "passive"))
      (node (ref "U22") (pin "12") (pinfunction "+OUT2_12") (pintype "passive"))
    )
    (net (code "69") (name "Net-(U22B--FB2)") (class "Default")
      (node (ref "R100") (pin "1") (pinfunction "1_1") (pintype "passive"))
      (node (ref "U22") (pin "5") (pinfunction "-FB2_5") (pintype "passive"))
    )
    (net (code "70") (name "Net-(U22B--IN2)") (class "Default")
      (node (ref "R104") (pin "1") (pinfunction "1_1") (pintype "passive"))
      (node (ref "R106") (pin "2") (pinfunction "2_2") (pintype "passive"))
      (node (ref "U22") (pin "7") (pinfunction "-IN2_7") (pintype "passive"))
    )
    (net (code "71") (name "Net-(U22B--OUT2)") (class "Default")
      (node (ref "L6") (pin "1") (pinfunction "1_1") (pintype "passive"))
      (node (ref "U22") (pin "13") (pinfunction "-OUT2_13") (pintype "passive"))
    )
    (net (code "72") (name "unconnected-(U21C-NC-Pad22)") (class "Default")
      (node (ref "U21") (pin "22") (pinfunction "NC_22") (pintype "passive+no_connect"))
    )
  )
)
